# Ex_Pin_Expander.net
KiCad netlist of a schematic drawn in EAGLE
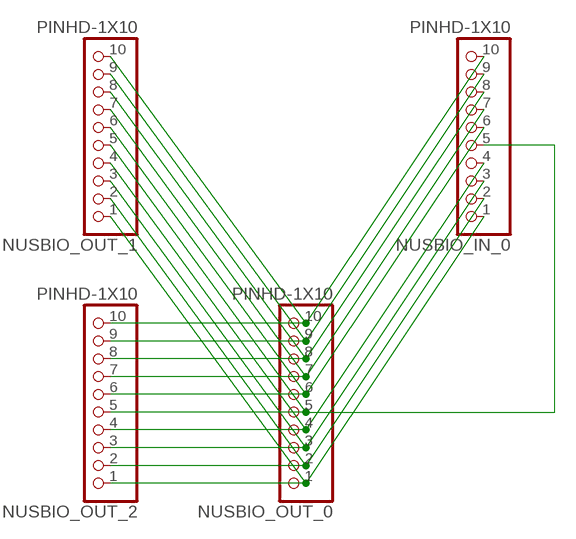
[diagram p0: schematic, sheet 1]

(export (version "E")
  (design (tool "Eeschema 10.0.6"))
  (components
    (comp (ref "NUSBIO_IN_0")
      (value "PINHD-1X10")
      (footprint "eagle-import:1X10-BIG")
      (libsource (lib "eagle-import") (part "PINHD-1X10"))
    )
    (comp (ref "NUSBIO_OUT_0")
      (value "PINHD-1X10")
      (footprint "eagle-import:1X10-BIG")
      (libsource (lib "eagle-import") (part "PINHD-1X10"))
    )
    (comp (ref "NUSBIO_OUT_1")
      (value "PINHD-1X10")
      (footprint "eagle-import:1X10-BIG")
      (libsource (lib "eagle-import") (part "PINHD-1X10"))
    )
    (comp (ref "NUSBIO_OUT_2")
      (value "PINHD-1X10")
      (footprint "eagle-import:1X10-BIG")
      (libsource (lib "eagle-import") (part "PINHD-1X10"))
    )
  )
  (nets
    (net (code "1") (name "Net-(NUSBIO_IN_0-Pad1)") (class "Default")
      (node (ref "NUSBIO_IN_0") (pin "1") (pinfunction "1_1") (pintype "passive"))
      (node (ref "NUSBIO_OUT_0") (pin "1") (pinfunction "1_1") (pintype "passive"))
      (node (ref "NUSBIO_OUT_1") (pin "1") (pinfunction "1_1") (pintype "passive"))
      (node (ref "NUSBIO_OUT_2") (pin "1") (pinfunction "1_1") (pintype "passive"))
    )
    (net (code "2") (name "Net-(NUSBIO_IN_0-Pad2)") (class "Default")
      (node (ref "NUSBIO_IN_0") (pin "2") (pinfunction "2_2") (pintype "passive"))
      (node (ref "NUSBIO_OUT_0") (pin "2") (pinfunction "2_2") (pintype "passive"))
      (node (ref "NUSBIO_OUT_1") (pin "2") (pinfunction "2_2") (pintype "passive"))
      (node (ref "NUSBIO_OUT_2") (pin "2") (pinfunction "2_2") (pintype "passive"))
    )
    (net (code "3") (name "Net-(NUSBIO_IN_0-Pad3)") (class "Default")
      (node (ref "NUSBIO_IN_0") (pin "3") (pinfunction "3_3") (pintype "passive"))
      (node (ref "NUSBIO_OUT_0") (pin "3") (pinfunction "3_3") (pintype "passive"))
      (node (ref "NUSBIO_OUT_1") (pin "3") (pinfunction "3_3") (pintype "passive"))
      (node (ref "NUSBIO_OUT_2") (pin "3") (pinfunction "3_3") (pintype "passive"))
    )
    (net (code "4") (name "Net-(NUSBIO_IN_0-Pad4)") (class "Default")
      (node (ref "NUSBIO_IN_0") (pin "4") (pinfunction "4_4") (pintype "passive"))
      (node (ref "NUSBIO_OUT_0") (pin "4") (pinfunction "4_4") (pintype "passive"))
      (node (ref "NUSBIO_OUT_1") (pin "4") (pinfunction "4_4") (pintype "passive"))
      (node (ref "NUSBIO_OUT_2") (pin "4") (pinfunction "4_4") (pintype "passive"))
    )
    (net (code "5") (name "Net-(NUSBIO_IN_0-Pad5)") (class "Default")
      (node (ref "NUSBIO_IN_0") (pin "5") (pinfunction "5_5") (pintype "passive"))
      (node (ref "NUSBIO_OUT_0") (pin "5") (pinfunction "5_5") (pintype "passive"))
      (node (ref "NUSBIO_OUT_1") (pin "5") (pinfunction "5_5") (pintype "passive"))
      (node (ref "NUSBIO_OUT_2") (pin "5") (pinfunction "5_5") (pintype "passive"))
    )
    (net (code "6") (name "Net-(NUSBIO_IN_0-Pad6)") (class "Default")
      (node (ref "NUSBIO_IN_0") (pin "6") (pinfunction "6_6") (pintype "passive"))
      (node (ref "NUSBIO_OUT_0") (pin "6") (pinfunction "6_6") (pintype "passive"))
      (node (ref "NUSBIO_OUT_1") (pin "6") (pinfunction "6_6") (pintype "passive"))
      (node (ref "NUSBIO_OUT_2") (pin "6") (pinfunction "6_6") (pintype "passive"))
    )
    (net (code "7") (name "Net-(NUSBIO_IN_0-Pad7)") (class "Default")
      (node (ref "NUSBIO_IN_0") (pin "7") (pinfunction "7_7") (pintype "passive"))
      (node (ref "NUSBIO_OUT_0") (pin "7") (pinfunction "7_7") (pintype "passive"))
      (node (ref "NUSBIO_OUT_1") (pin "7") (pinfunction "7_7") (pintype "passive"))
      (node (ref "NUSBIO_OUT_2") (pin "7") (pinfunction "7_7") (pintype "passive"))
    )
    (net (code "8") (name "Net-(NUSBIO_IN_0-Pad8)") (class "Default")
      (node (ref "NUSBIO_IN_0") (pin "8") (pinfunction "8_8") (pintype "passive"))
      (node (ref "NUSBIO_OUT_0") (pin "8") (pinfunction "8_8") (pintype "passive"))
      (node (ref "NUSBIO_OUT_1") (pin "8") (pinfunction "8_8") (pintype "passive"))
      (node (ref "NUSBIO_OUT_2") (pin "8") (pinfunction "8_8") (pintype "passive"))
    )
    (net (code "9") (name "Net-(NUSBIO_IN_0-Pad9)") (class "Default")
      (node (ref "NUSBIO_IN_0") (pin "9") (pinfunction "9_9") (pintype "passive"))
      (node (ref "NUSBIO_OUT_0") (pin "9") (pinfunction "9_9") (pintype "passive"))
      (node (ref "NUSBIO_OUT_1") (pin "9") (pinfunction "9_9") (pintype "passive"))
      (node (ref "NUSBIO_OUT_2") (pin "9") (pinfunction "9_9") (pintype "passive"))
    )
    (net (code "10") (name "Net-(NUSBIO_IN_0-Pad10)") (class "Default")
      (node (ref "NUSBIO_IN_0") (pin "10") (pinfunction "10_10") (pintype "passive"))
      (node (ref "NUSBIO_OUT_0") (pin "10") (pinfunction "10_10") (pintype "passive"))
      (node (ref "NUSBIO_OUT_1") (pin "10") (pinfunction "10_10") (pintype "passive"))
      (node (ref "NUSBIO_OUT_2") (pin "10") (pinfunction "10_10") (pintype "passive"))
    )
  )
)
